# strain-gauge-amplifier.net
KiCad netlist of a schematic drawn in EAGLE
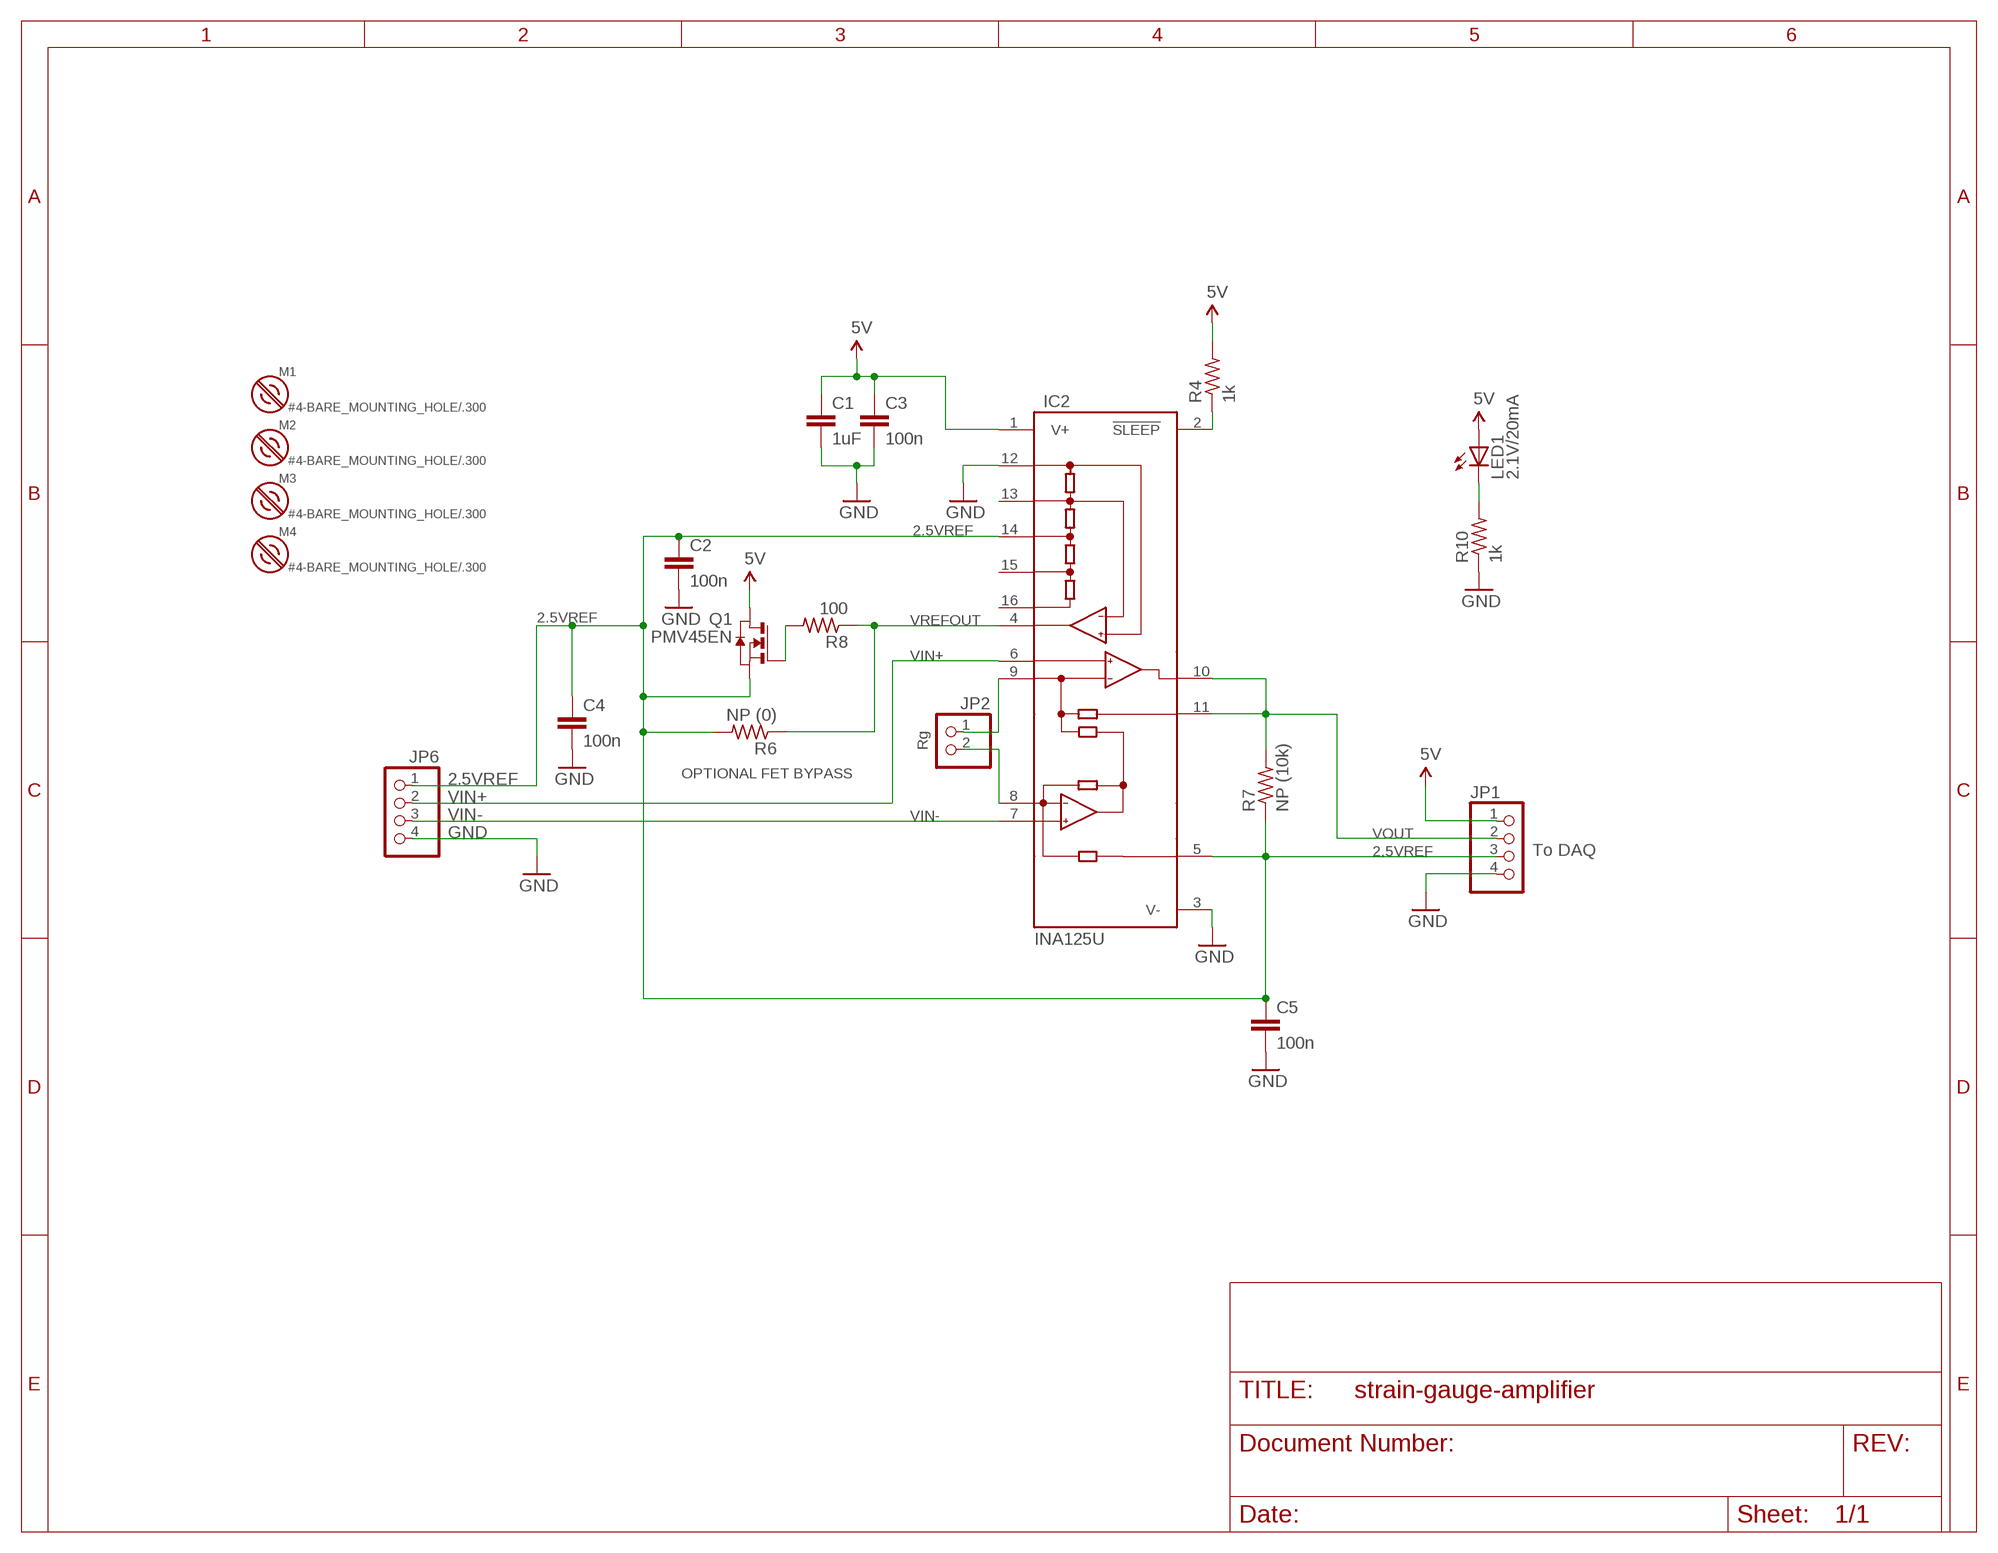
[diagram p0: schematic, sheet 1]

(export (version "E")
  (design (tool "Eeschema 10.0.6"))
  (components
    (comp (ref "C1")
      (value "1uF")
      (footprint "eagle-import:0805-C-NOSILK")
      (libsource (lib "eagle-import") (part "C-EU0805-C-NOSILK"))
    )
    (comp (ref "C2")
      (value "100n")
      (footprint "eagle-import:0805-C-NOSILK")
      (libsource (lib "eagle-import") (part "C-EU0805-C-NOSILK"))
    )
    (comp (ref "C3")
      (value "100n")
      (footprint "eagle-import:0805-C-NOSILK")
      (libsource (lib "eagle-import") (part "C-EU0805-C-NOSILK"))
    )
    (comp (ref "C4")
      (value "100n")
      (footprint "eagle-import:0805-C-NOSILK")
      (libsource (lib "eagle-import") (part "C-EU0805-C-NOSILK"))
    )
    (comp (ref "C5")
      (value "100n")
      (footprint "eagle-import:0805-C-NOSILK")
      (libsource (lib "eagle-import") (part "C-EU0805-C-NOSILK"))
    )
    (comp (ref "IC2")
      (value "INA125U")
      (footprint "eagle-import:SO16-1")
      (fields (field (name "MF") "TEXAS INSTRUMENT CONNECTORS"))
      (libsource (lib "eagle-import") (part "INA125U"))
    )
    (comp (ref "JP1")
      (value "PINHD-1X4")
      (footprint "eagle-import:1X04")
      (libsource (lib "eagle-import") (part "PINHD-1X4"))
    )
    (comp (ref "JP2")
      (value "PINHD-1X2")
      (footprint "eagle-import:1X02")
      (libsource (lib "eagle-import") (part "PINHD-1X2"))
    )
    (comp (ref "JP6")
      (value "PINHD-1X4")
      (footprint "eagle-import:1X04")
      (libsource (lib "eagle-import") (part "PINHD-1X4"))
    )
    (comp (ref "LED1")
      (value "2.1V/20mA")
      (footprint "eagle-import:LED-0603")
      (libsource (lib "eagle-import") (part "LED0603"))
    )
    (comp (ref "M1")
      (value "#4-BARE_MOUNTING_HOLE/.300")
      (footprint "eagle-import:#4_.300-BARE+STD_NUT_OR_STAR_WASHER")
      (libsource (lib "eagle-import") (part "#4-BARE_MOUNTING_HOLE/.300"))
    )
    (comp (ref "M2")
      (value "#4-BARE_MOUNTING_HOLE/.300")
      (footprint "eagle-import:#4_.300-BARE+STD_NUT_OR_STAR_WASHER")
      (libsource (lib "eagle-import") (part "#4-BARE_MOUNTING_HOLE/.300"))
    )
    (comp (ref "M3")
      (value "#4-BARE_MOUNTING_HOLE/.300")
      (footprint "eagle-import:#4_.300-BARE+STD_NUT_OR_STAR_WASHER")
      (libsource (lib "eagle-import") (part "#4-BARE_MOUNTING_HOLE/.300"))
    )
    (comp (ref "M4")
      (value "#4-BARE_MOUNTING_HOLE/.300")
      (footprint "eagle-import:#4_.300-BARE+STD_NUT_OR_STAR_WASHER")
      (libsource (lib "eagle-import") (part "#4-BARE_MOUNTING_HOLE/.300"))
    )
    (comp (ref "Q1")
      (value "PMV45EN")
      (footprint "eagle-import:SOT23")
      (libsource (lib "eagle-import") (part "PMV45EN"))
    )
    (comp (ref "R4")
      (value "1k")
      (footprint "eagle-import:0805-C-NOSILK")
      (libsource (lib "eagle-import") (part "R-US_0805-C-NOSILK"))
    )
    (comp (ref "R6")
      (value "NP (0)")
      (footprint "eagle-import:0805-C-NOSILK")
      (libsource (lib "eagle-import") (part "R-US_0805-C-NOSILK"))
    )
    (comp (ref "R7")
      (value "NP (10k)")
      (footprint "eagle-import:0805-C-NOSILK")
      (libsource (lib "eagle-import") (part "R-US_0805-C-NOSILK"))
    )
    (comp (ref "R8")
      (value "100")
      (footprint "eagle-import:0805-C-NOSILK")
      (libsource (lib "eagle-import") (part "R-US_0805-C-NOSILK"))
    )
    (comp (ref "R10")
      (value "1k")
      (footprint "eagle-import:0805-C-NOSILK")
      (libsource (lib "eagle-import") (part "R-US_0805-C-NOSILK"))
    )
  )
  (nets
    (net (code "1") (name "/2.5VREF") (class "Default")
      (node (ref "C2") (pin "1") (pinfunction "1_1") (pintype "passive"))
      (node (ref "C4") (pin "1") (pinfunction "1_1") (pintype "passive"))
      (node (ref "C5") (pin "1") (pinfunction "1_1") (pintype "passive"))
      (node (ref "IC2") (pin "14") (pinfunction "REF2.5_14") (pintype "output"))
      (node (ref "IC2") (pin "5") (pinfunction "REF_5") (pintype "passive"))
      (node (ref "JP1") (pin "3") (pinfunction "3_3") (pintype "passive"))
      (node (ref "JP6") (pin "1") (pinfunction "1_1") (pintype "passive"))
      (node (ref "Q1") (pin "2") (pinfunction "S_2") (pintype "passive"))
      (node (ref "R6") (pin "2") (pinfunction "2_2") (pintype "passive"))
      (node (ref "R7") (pin "1") (pinfunction "1_1") (pintype "passive"))
    )
    (net (code "2") (name "/VIN+") (class "Default")
      (node (ref "IC2") (pin "6") (pinfunction "+IN_6") (pintype "input"))
      (node (ref "JP6") (pin "2") (pinfunction "2_2") (pintype "passive"))
    )
    (net (code "3") (name "/VIN-") (class "Default")
      (node (ref "IC2") (pin "7") (pinfunction "-VIN_7") (pintype "input"))
      (node (ref "JP6") (pin "3") (pinfunction "3_3") (pintype "passive"))
    )
    (net (code "4") (name "/VOUT") (class "Default")
      (node (ref "IC2") (pin "10") (pinfunction "OUT_10") (pintype "output"))
      (node (ref "IC2") (pin "11") (pinfunction "SENSE_11") (pintype "passive"))
      (node (ref "JP1") (pin "2") (pinfunction "2_2") (pintype "passive"))
      (node (ref "R7") (pin "2") (pinfunction "2_2") (pintype "passive"))
    )
    (net (code "5") (name "/VREFOUT") (class "Default")
      (node (ref "IC2") (pin "4") (pinfunction "REFOUT_4") (pintype "output"))
      (node (ref "R6") (pin "1") (pinfunction "1_1") (pintype "passive"))
      (node (ref "R8") (pin "1") (pinfunction "1_1") (pintype "passive"))
    )
    (net (code "6") (name "5V") (class "Default")
      (node (ref "C1") (pin "1") (pinfunction "1_1") (pintype "passive"))
      (node (ref "C3") (pin "1") (pinfunction "1_1") (pintype "passive"))
      (node (ref "IC2") (pin "1") (pinfunction "V+_1") (pintype "power_in"))
      (node (ref "JP1") (pin "1") (pinfunction "1_1") (pintype "passive"))
      (node (ref "LED1") (pin "A") (pinfunction "A_A") (pintype "passive"))
      (node (ref "Q1") (pin "3") (pinfunction "D_3") (pintype "passive"))
      (node (ref "R4") (pin "2") (pinfunction "2_2") (pintype "passive"))
    )
    (net (code "7") (name "GND") (class "Default")
      (node (ref "C1") (pin "2") (pinfunction "2_2") (pintype "passive"))
      (node (ref "C2") (pin "2") (pinfunction "2_2") (pintype "passive"))
      (node (ref "C3") (pin "2") (pinfunction "2_2") (pintype "passive"))
      (node (ref "C4") (pin "2") (pinfunction "2_2") (pintype "passive"))
      (node (ref "C5") (pin "2") (pinfunction "2_2") (pintype "passive"))
      (node (ref "IC2") (pin "12") (pinfunction "REFCOM_12") (pintype "passive"))
      (node (ref "IC2") (pin "3") (pinfunction "V-_3") (pintype "power_in"))
      (node (ref "JP1") (pin "4") (pinfunction "4_4") (pintype "passive"))
      (node (ref "JP6") (pin "4") (pinfunction "4_4") (pintype "passive"))
      (node (ref "R10") (pin "1") (pinfunction "1_1") (pintype "passive"))
    )
    (net (code "8") (name "Net-(IC2-RG-Pad8)") (class "Default")
      (node (ref "IC2") (pin "8") (pinfunction "RG_8") (pintype "passive"))
      (node (ref "JP2") (pin "2") (pinfunction "2_2") (pintype "passive"))
    )
    (net (code "9") (name "Net-(IC2-RG-Pad9)") (class "Default")
      (node (ref "IC2") (pin "9") (pinfunction "RG_9") (pintype "passive"))
      (node (ref "JP2") (pin "1") (pinfunction "1_1") (pintype "passive"))
    )
    (net (code "10") (name "Net-(IC2-~{SLEEP})") (class "Default")
      (node (ref "IC2") (pin "2") (pinfunction "~{SLEEP}_2") (pintype "input"))
      (node (ref "R4") (pin "1") (pinfunction "1_1") (pintype "passive"))
    )
    (net (code "11") (name "Net-(LED1-PadC)") (class "Default")
      (node (ref "LED1") (pin "C") (pinfunction "C_C") (pintype "passive"))
      (node (ref "R10") (pin "2") (pinfunction "2_2") (pintype "passive"))
    )
    (net (code "12") (name "Net-(Q1-G)") (class "Default")
      (node (ref "Q1") (pin "1") (pinfunction "G_1") (pintype "passive"))
      (node (ref "R8") (pin "2") (pinfunction "2_2") (pintype "passive"))
    )
    (net (code "13") (name "unconnected-(IC2-REF5-Pad15)") (class "Default")
      (node (ref "IC2") (pin "15") (pinfunction "REF5_15") (pintype "output"))
    )
    (net (code "14") (name "unconnected-(IC2-REF10-Pad16)") (class "Default")
      (node (ref "IC2") (pin "16") (pinfunction "REF10_16") (pintype "output"))
    )
    (net (code "15") (name "unconnected-(IC2-REFBG-Pad13)") (class "Default")
      (node (ref "IC2") (pin "13") (pinfunction "REFBG_13") (pintype "output"))
    )
  )
)
